# Controller.net
KiCad netlist of a schematic drawn in Altium Designer
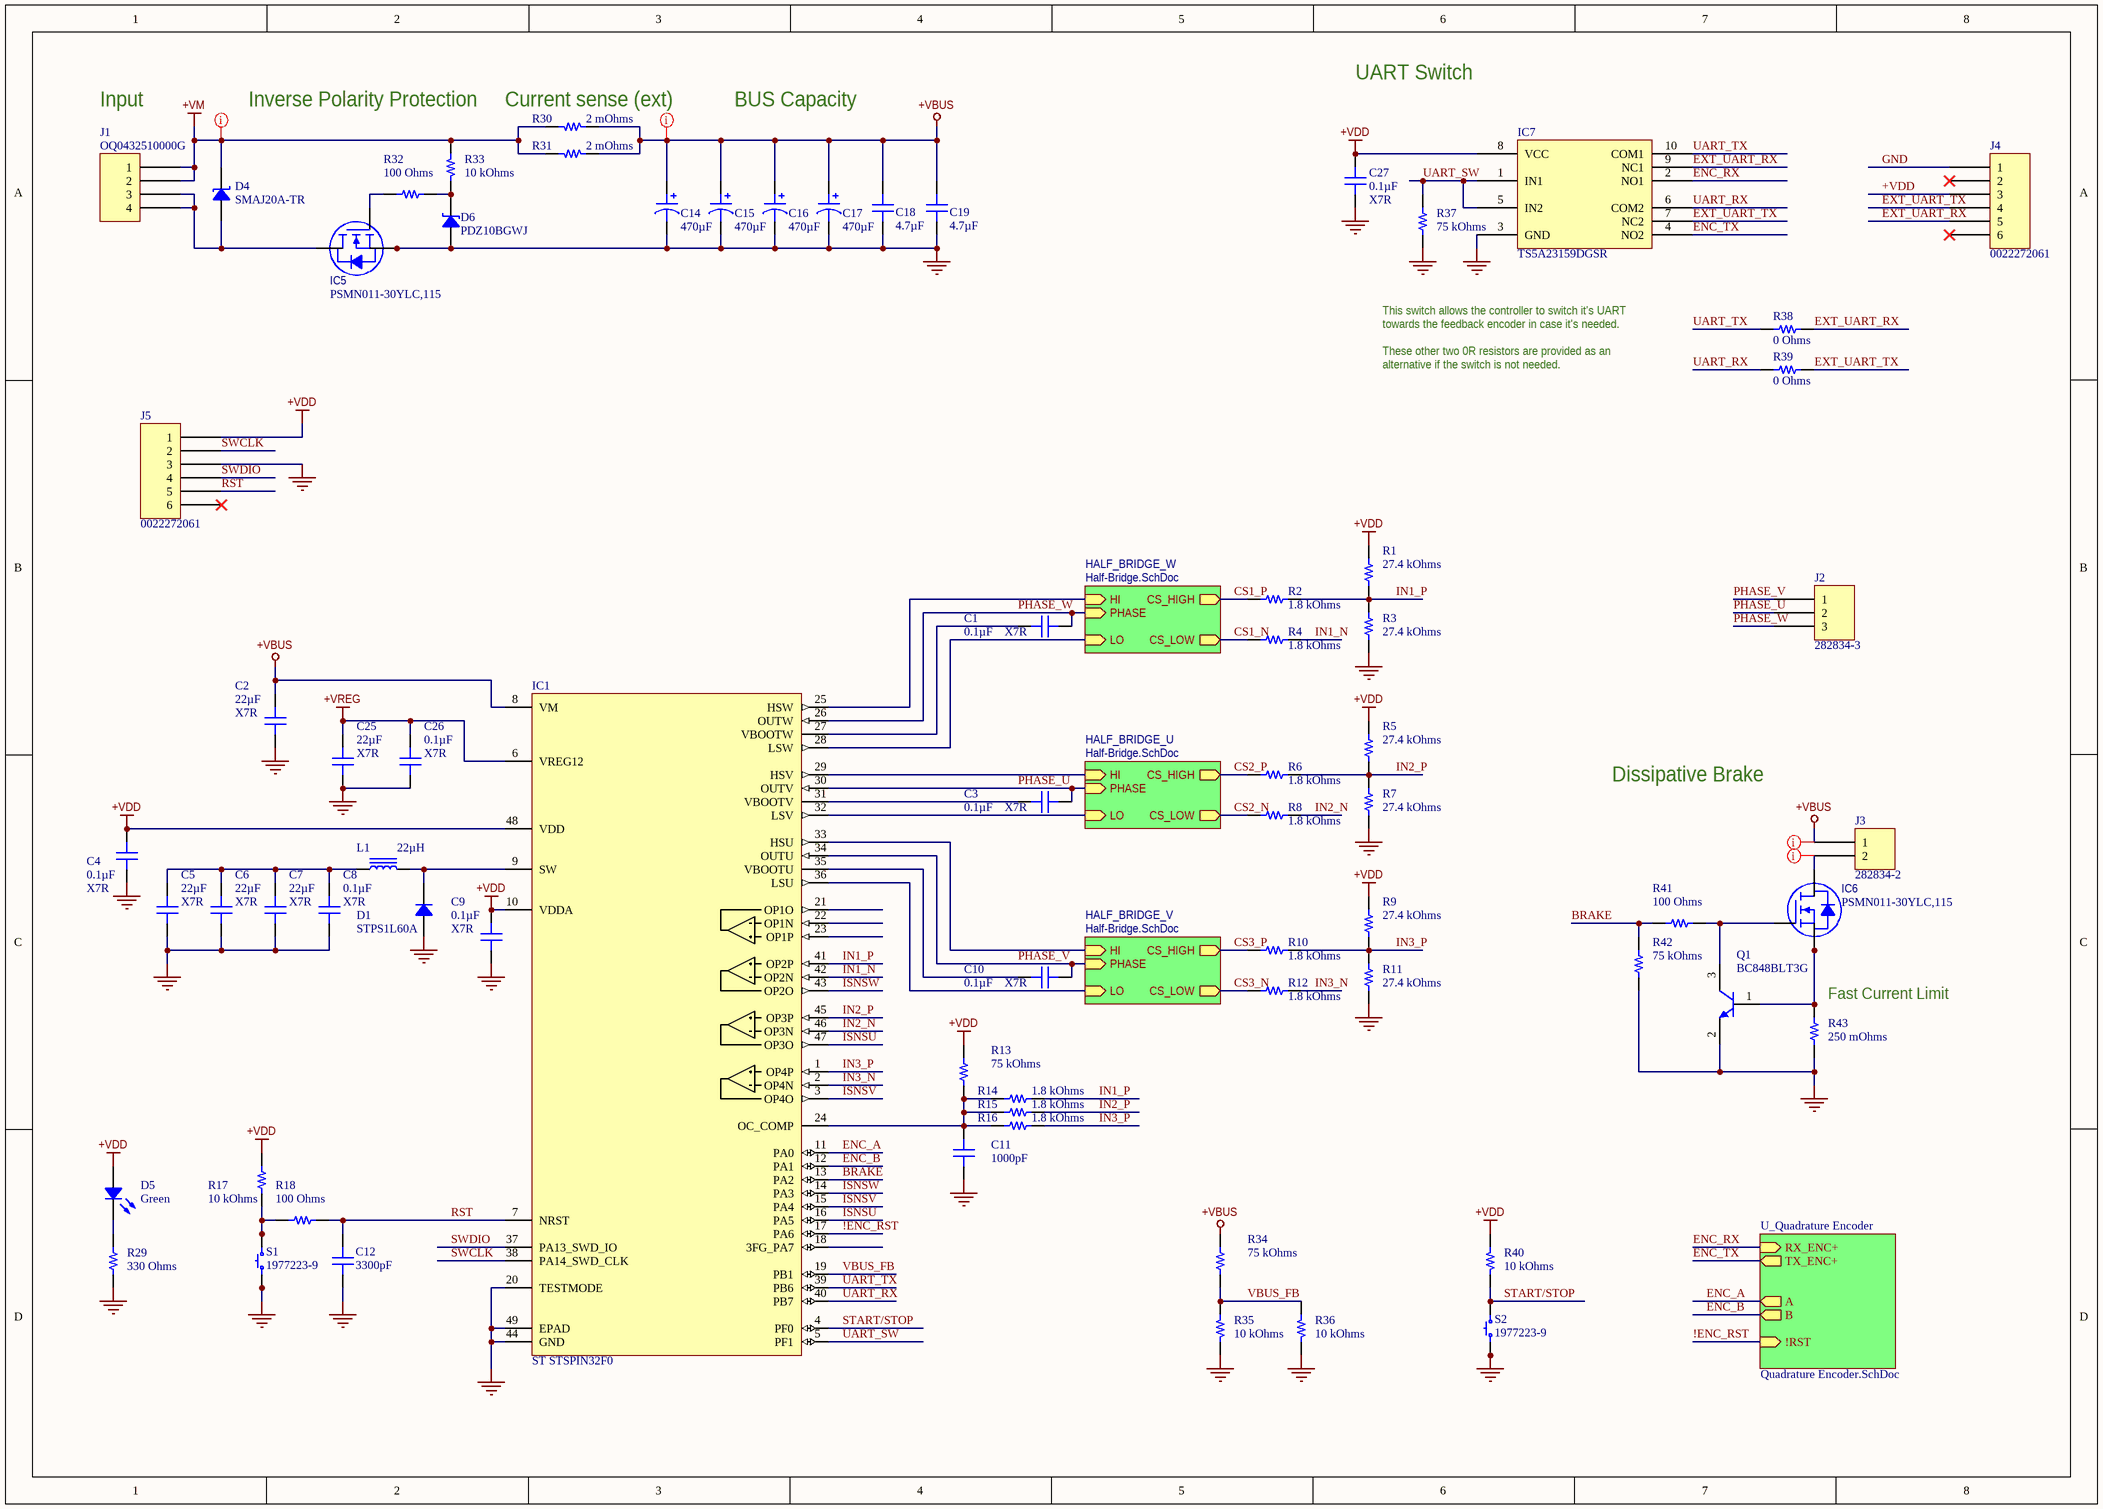
[diagram p0: Controller.SchDoc]

(export (version "E")
  (design (tool "Eeschema 10.0.6"))
  (components
    (comp (ref "C1")
      (value "0.1µF")
      (footprint "CAP 0805_2012")
      (description "CAP CER 0.1UF 50V X7R 0805")
      (fields
        (field (name "PART NUMBER") "CL21B104KBCWPNC")
        (field (name "MANUFACTURER") "Samsung Electro-Mechanics")
        (field (name "TEMPERATURE COEFFICIENT") "X7R")
      )
      (libsource (lib "Celestial Altium Library - altium_library") (part "Capacitor"))
    )
    (comp (ref "C2")
      (value "22µF")
      (footprint "CAP 1206_3216 - 1.8MM")
      (description "CAP CER 22UF 6.3V X7R 1206")
      (fields
        (field (name "PART NUMBER") "GCM31CR70J226KE23L")
        (field (name "MANUFACTURER") "Murata Electronics")
        (field (name "TEMPERATURE COEFFICIENT") "X7R")
      )
      (libsource (lib "Celestial Altium Library - altium_library") (part "Capacitor"))
    )
    (comp (ref "C3")
      (value "0.1µF")
      (footprint "CAP 0805_2012")
      (description "CAP CER 0.1UF 50V X7R 0805")
      (fields
        (field (name "PART NUMBER") "CL21B104KBCWPNC")
        (field (name "MANUFACTURER") "Samsung Electro-Mechanics")
        (field (name "TEMPERATURE COEFFICIENT") "X7R")
      )
      (libsource (lib "Celestial Altium Library - altium_library") (part "Capacitor"))
    )
    (comp (ref "C4")
      (value "0.1µF")
      (footprint "CAP 0805_2012")
      (description "CAP CER 0.1UF 50V X7R 0805")
      (fields
        (field (name "PART NUMBER") "CL21B104KBCWPNC")
        (field (name "MANUFACTURER") "Samsung Electro-Mechanics")
        (field (name "TEMPERATURE COEFFICIENT") "X7R")
      )
      (libsource (lib "Celestial Altium Library - altium_library") (part "Capacitor"))
    )
    (comp (ref "C5")
      (value "22µF")
      (footprint "CAP 1206_3216 - 1.8MM")
      (description "CAP CER 22UF 6.3V X7R 1206")
      (fields
        (field (name "PART NUMBER") "GCM31CR70J226KE23L")
        (field (name "MANUFACTURER") "Murata Electronics")
        (field (name "TEMPERATURE COEFFICIENT") "X7R")
      )
      (libsource (lib "Celestial Altium Library - altium_library") (part "Capacitor"))
    )
    (comp (ref "C6")
      (value "22µF")
      (footprint "CAP 1206_3216 - 1.8MM")
      (description "CAP CER 22UF 6.3V X7R 1206")
      (fields
        (field (name "PART NUMBER") "GCM31CR70J226KE23L")
        (field (name "MANUFACTURER") "Murata Electronics")
        (field (name "TEMPERATURE COEFFICIENT") "X7R")
      )
      (libsource (lib "Celestial Altium Library - altium_library") (part "Capacitor"))
    )
    (comp (ref "C7")
      (value "22µF")
      (footprint "CAP 1206_3216 - 1.8MM")
      (description "CAP CER 22UF 6.3V X7R 1206")
      (fields
        (field (name "PART NUMBER") "GCM31CR70J226KE23L")
        (field (name "MANUFACTURER") "Murata Electronics")
        (field (name "TEMPERATURE COEFFICIENT") "X7R")
      )
      (libsource (lib "Celestial Altium Library - altium_library") (part "Capacitor"))
    )
    (comp (ref "C8")
      (value "0.1µF")
      (footprint "CAP 0805_2012")
      (description "CAP CER 0.1UF 50V X7R 0805")
      (fields
        (field (name "PART NUMBER") "CL21B104KBCWPNC")
        (field (name "MANUFACTURER") "Samsung Electro-Mechanics")
        (field (name "TEMPERATURE COEFFICIENT") "X7R")
      )
      (libsource (lib "Celestial Altium Library - altium_library") (part "Capacitor"))
    )
    (comp (ref "C9")
      (value "0.1µF")
      (footprint "CAP 0805_2012")
      (description "CAP CER 0.1UF 50V X7R 0805")
      (fields
        (field (name "PART NUMBER") "CL21B104KBCWPNC")
        (field (name "MANUFACTURER") "Samsung Electro-Mechanics")
        (field (name "TEMPERATURE COEFFICIENT") "X7R")
      )
      (libsource (lib "Celestial Altium Library - altium_library") (part "Capacitor"))
    )
    (comp (ref "C10")
      (value "0.1µF")
      (footprint "CAP 0805_2012")
      (description "CAP CER 0.1UF 50V X7R 0805")
      (fields
        (field (name "PART NUMBER") "CL21B104KBCWPNC")
        (field (name "MANUFACTURER") "Samsung Electro-Mechanics")
        (field (name "TEMPERATURE COEFFICIENT") "X7R")
      )
      (libsource (lib "Celestial Altium Library - altium_library") (part "Capacitor"))
    )
    (comp (ref "C11")
      (value "1000pF")
      (footprint "CAP 0603_1608")
      (description "CAP CER 0603 1NF 16V X7R 10%")
      (fields (field (name "PART NUMBER") "C0603C102K4RECAUTO") (field (name "MANUFACTURER") "KEMET"))
      (libsource (lib "Celestial Altium Library - altium_library") (part "Capacitor"))
    )
    (comp (ref "C12")
      (value "3300pF")
      (footprint "CAP 0603_1608")
      (description "CAP CER 3300PF 25V NP0 0603")
      (fields (field (name "PART NUMBER") "C0603C332J3GAC7867") (field (name "MANUFACTURER") "KEMET"))
      (libsource (lib "Celestial Altium Library - altium_library") (part "Capacitor"))
    )
    (comp (ref "C14")
      (value "470µF")
      (footprint "CAP ALSMD 8.3MM H10.5MM")
      (description "CAP ALUM 470UF 20% 25V SMD")
      (fields (field (name "PART NUMBER") "25TPV470M8X10.5") (field (name "MANUFACTURER") "Rubycon"))
      (libsource (lib "Celestial Altium Library - altium_library") (part "Polarised Capacitor"))
    )
    (comp (ref "C15")
      (value "470µF")
      (footprint "CAP ALSMD 8.3MM H10.5MM")
      (description "CAP ALUM 470UF 20% 25V SMD")
      (fields (field (name "PART NUMBER") "25TPV470M8X10.5") (field (name "MANUFACTURER") "Rubycon"))
      (libsource (lib "Celestial Altium Library - altium_library") (part "Polarised Capacitor"))
    )
    (comp (ref "C16")
      (value "470µF")
      (footprint "CAP ALSMD 8.3MM H10.5MM")
      (description "CAP ALUM 470UF 20% 25V SMD")
      (fields (field (name "PART NUMBER") "25TPV470M8X10.5") (field (name "MANUFACTURER") "Rubycon"))
      (libsource (lib "Celestial Altium Library - altium_library") (part "Polarised Capacitor"))
    )
    (comp (ref "C17")
      (value "470µF")
      (footprint "CAP ALSMD 8.3MM H10.5MM")
      (description "CAP ALUM 470UF 20% 25V SMD")
      (fields (field (name "PART NUMBER") "25TPV470M8X10.5") (field (name "MANUFACTURER") "Rubycon"))
      (libsource (lib "Celestial Altium Library - altium_library") (part "Polarised Capacitor"))
    )
    (comp (ref "C18")
      (value "4.7µF")
      (footprint "CAP 1206_3216 - 1.8MM")
      (description "CAP CER 4.7UF 25V X7R 1206")
      (fields
        (field (name "PART NUMBER") "GCM31CR71E475KA55L")
        (field (name "MANUFACTURER") "Murata Electronics")
      )
      (libsource (lib "Celestial Altium Library - altium_library") (part "Capacitor"))
    )
    (comp (ref "C19")
      (value "4.7µF")
      (footprint "CAP 1206_3216 - 1.8MM")
      (description "CAP CER 4.7UF 25V X7R 1206")
      (fields
        (field (name "PART NUMBER") "GCM31CR71E475KA55L")
        (field (name "MANUFACTURER") "Murata Electronics")
      )
      (libsource (lib "Celestial Altium Library - altium_library") (part "Capacitor"))
    )
    (comp (ref "C25")
      (value "22µF")
      (footprint "CAP 1206_3216 - 1.8MM")
      (description "CAP CER 22UF 6.3V X7R 1206")
      (fields
        (field (name "PART NUMBER") "GCM31CR70J226KE23L")
        (field (name "MANUFACTURER") "Murata Electronics")
        (field (name "TEMPERATURE COEFFICIENT") "X7R")
      )
      (libsource (lib "Celestial Altium Library - altium_library") (part "Capacitor"))
    )
    (comp (ref "C26")
      (value "0.1µF")
      (footprint "CAP 0805_2012")
      (description "CAP CER 0.1UF 50V X7R 0805")
      (fields
        (field (name "PART NUMBER") "CL21B104KBCWPNC")
        (field (name "MANUFACTURER") "Samsung Electro-Mechanics")
        (field (name "TEMPERATURE COEFFICIENT") "X7R")
      )
      (libsource (lib "Celestial Altium Library - altium_library") (part "Capacitor"))
    )
    (comp (ref "C27")
      (value "0.1µF")
      (footprint "CAP 0805_2012")
      (description "CAP CER 0.1UF 50V X7R 0805")
      (fields
        (field (name "PART NUMBER") "CL21B104KBCWPNC")
        (field (name "MANUFACTURER") "Samsung Electro-Mechanics")
        (field (name "TEMPERATURE COEFFICIENT") "X7R")
      )
      (libsource (lib "Celestial Altium Library - altium_library") (part "Capacitor"))
    )
    (comp (ref "D1")
      (value "STPS1L60A")
      (footprint "DO214AC SMA")
      (description "DIODE SCHOTTKY 60V 1A SMA")
      (fields (field (name "MANUFACTURER") "STMicroelectronics"))
      (libsource (lib "Celestial Altium Library - altium_library") (part "Diode"))
    )
    (comp (ref "D4")
      (value "SMAJ20A-TR")
      (footprint "DO214AC SMA")
      (description "TVS DIODE 20V 42.8V SMA")
      (fields (field (name "MANUFACTURER") "STMicroelectronics"))
      (libsource (lib "Celestial Altium Library - altium_library") (part "DIODE TVS UNI"))
    )
    (comp (ref "D5")
      (value "Green")
      (footprint "LED 0603_1608 GREEN")
      (description "LED GREEN DIFFUSED 0603 SMD")
      (fields (field (name "PART NUMBER") "SML-D12P8WT86") (field (name "MANUFACTURER") "Rohm Semiconductor"))
      (libsource (lib "Celestial Altium Library - altium_library") (part "LED"))
    )
    (comp (ref "D6")
      (value "PDZ10BGWJ")
      (footprint "SOD-123")
      (description "DIODE ZENER 10V 365MW SOD123")
      (fields (field (name "MANUFACTURER") "Nexperia USA Inc.") (field (name "TOLERANCE") "±2.2%"))
      (libsource (lib "Celestial Altium Library - altium_library") (part "Diode Zener"))
    )
    (comp (ref "IC1")
      (value "ST STSPIN32F0")
      (footprint "PCB - LEADLESS - QFN - ST VFQFPN48 EP 5x5MM:ST VFQFPN48EP 7x7MM")
      (libsource (lib "SCH - MICROCONTROLLER - ST STSPIN32F0") (part "ST STSPIN32F0"))
    )
    (comp (ref "IC5")
      (value "PSMN011-30YLC,115")
      (footprint "NXP LFPAK56 SOT669")
      (description "MOSFET N-CH 30V 37A LFPAK")
      (fields (field (name "MANUFACTURER") "Nexperia USA Inc."))
      (libsource (lib "") (part "NEXPERIA PSMN LFPAK MOSFET N-CH_1"))
    )
    (comp (ref "IC6")
      (value "PSMN011-30YLC,115")
      (footprint "NXP LFPAK56 SOT669")
      (description "MOSFET N-CH 30V 37A LFPAK")
      (fields (field (name "MANUFACTURER") "Nexperia USA Inc."))
      (libsource (lib "Celestial Altium Library - altium_library") (part "NEXPERIA PSMN LFPAK MOSFET N-CH"))
    )
    (comp (ref "IC7")
      (value "TS5A23159DGSR")
      (footprint "TI MSOP-10 DGS")
      (description "IC SWITCH SPDT DUAL 10VSSOP")
      (fields (field (name "MANUFACTURER") "Texas Instruments"))
      (libsource (lib "Celestial Altium Library - altium_library") (part "TI TS5A23159"))
    )
    (comp (ref "J1")
      (value "OQ0432510000G")
      (footprint "FCI 06-381-4PIN")
      (description "TERM BLOCK HDR 4POS 90DEG 3.81MM")
      (fields (field (name "MANUFACTURER") "Amphenol Anytek"))
      (libsource (lib "Celestial Altium Library - altium_library") (part "4 Pin"))
    )
    (comp (ref "J2")
      (value "282834-3")
      (footprint "TE 282834-3")
      (description "TERM BLK 3P SIDE ENT 2.54MM PCB")
      (fields (field (name "MANUFACTURER") "TE Connectivity AMP Connectors") (field (name "VOLTAGE") "150V"))
      (libsource (lib "Celestial Altium Library - altium_library") (part "3 Pin"))
    )
    (comp (ref "J3")
      (value "282834-2")
      (footprint "TE 282834-2")
      (description "TERM BLK 2P SIDE ENT 2.54MM PCB")
      (fields (field (name "MANUFACTURER") "TE Connectivity AMP Connectors") (field (name "VOLTAGE") "150V"))
      (libsource (lib "Celestial Altium Library - altium_library") (part "2 Pin"))
    )
    (comp (ref "J4")
      (value "0022272061")
      (footprint "MOLEX KK 0022272061")
      (description "CONN HEADER VERT 6POS 2.54MM")
      (fields (field (name "MANUFACTURER") "Molex"))
      (libsource (lib "Celestial Altium Library - altium_library") (part "6 Pin"))
    )
    (comp (ref "J5")
      (value "0022272061")
      (footprint "MOLEX KK 0022272061")
      (description "CONN HEADER VERT 6POS 2.54MM")
      (fields (field (name "MANUFACTURER") "Molex"))
      (libsource (lib "") (part "6 Pin_1"))
    )
    (comp (ref "L1")
      (value "22µH")
      (footprint "BOURNS SRN3015")
      (description "FIXED IND 22UH 600MA 622MOHM SMD")
      (fields (field (name "PART NUMBER") "SRN3015-220M") (field (name "MANUFACTURER") "Bourns Inc."))
      (libsource (lib "Celestial Altium Library - altium_library") (part "Inductor"))
    )
    (comp (ref "Q1")
      (value "BC848BLT3G")
      (footprint "ON SEMI SOT-23-3")
      (description "TRANS NPN 30V 0.1A SOT-23")
      (fields (field (name "MANUFACTURER") "ON Semiconductor"))
      (libsource (lib "Celestial Altium Library - altium_library") (part "ON SEMI NPN SOT-23-3"))
    )
    (comp (ref "R1")
      (value "27.4 kOhms")
      (footprint "RES 0603_1608")
      (description "RES SMD 27.4K OHM 1% 1/10W 0603")
      (fields
        (field (name "PART NUMBER") "ERJ-3EKF2742V")
        (field (name "MANUFACTURER") "Panasonic Electronic Components")
      )
      (libsource (lib "Celestial Altium Library - altium_library") (part "Resistor"))
    )
    (comp (ref "R2")
      (value "1.8 kOhms")
      (footprint "RES 0603_1608")
      (description "RES SMD 1.8K OHM 1% 1/4W 0603")
      (fields
        (field (name "PART NUMBER") "ERJ-PA3F1801V")
        (field (name "MANUFACTURER") "Panasonic Electronic Components")
      )
      (libsource (lib "Celestial Altium Library - altium_library") (part "Resistor"))
    )
    (comp (ref "R3")
      (value "27.4 kOhms")
      (footprint "RES 0603_1608")
      (description "RES SMD 27.4K OHM 1% 1/10W 0603")
      (fields
        (field (name "PART NUMBER") "ERJ-3EKF2742V")
        (field (name "MANUFACTURER") "Panasonic Electronic Components")
      )
      (libsource (lib "Celestial Altium Library - altium_library") (part "Resistor"))
    )
    (comp (ref "R4")
      (value "1.8 kOhms")
      (footprint "RES 0603_1608")
      (description "RES SMD 1.8K OHM 1% 1/4W 0603")
      (fields
        (field (name "PART NUMBER") "ERJ-PA3F1801V")
        (field (name "MANUFACTURER") "Panasonic Electronic Components")
      )
      (libsource (lib "Celestial Altium Library - altium_library") (part "Resistor"))
    )
    (comp (ref "R5")
      (value "27.4 kOhms")
      (footprint "RES 0603_1608")
      (description "RES SMD 27.4K OHM 1% 1/10W 0603")
      (fields
        (field (name "PART NUMBER") "ERJ-3EKF2742V")
        (field (name "MANUFACTURER") "Panasonic Electronic Components")
      )
      (libsource (lib "Celestial Altium Library - altium_library") (part "Resistor"))
    )
    (comp (ref "R6")
      (value "1.8 kOhms")
      (footprint "RES 0603_1608")
      (description "RES SMD 1.8K OHM 1% 1/4W 0603")
      (fields
        (field (name "PART NUMBER") "ERJ-PA3F1801V")
        (field (name "MANUFACTURER") "Panasonic Electronic Components")
      )
      (libsource (lib "Celestial Altium Library - altium_library") (part "Resistor"))
    )
    (comp (ref "R7")
      (value "27.4 kOhms")
      (footprint "RES 0603_1608")
      (description "RES SMD 27.4K OHM 1% 1/10W 0603")
      (fields
        (field (name "PART NUMBER") "ERJ-3EKF2742V")
        (field (name "MANUFACTURER") "Panasonic Electronic Components")
      )
      (libsource (lib "Celestial Altium Library - altium_library") (part "Resistor"))
    )
    (comp (ref "R8")
      (value "1.8 kOhms")
      (footprint "RES 0603_1608")
      (description "RES SMD 1.8K OHM 1% 1/4W 0603")
      (fields
        (field (name "PART NUMBER") "ERJ-PA3F1801V")
        (field (name "MANUFACTURER") "Panasonic Electronic Components")
      )
      (libsource (lib "Celestial Altium Library - altium_library") (part "Resistor"))
    )
    (comp (ref "R9")
      (value "27.4 kOhms")
      (footprint "RES 0603_1608")
      (description "RES SMD 27.4K OHM 1% 1/10W 0603")
      (fields
        (field (name "PART NUMBER") "ERJ-3EKF2742V")
        (field (name "MANUFACTURER") "Panasonic Electronic Components")
      )
      (libsource (lib "Celestial Altium Library - altium_library") (part "Resistor"))
    )
    (comp (ref "R10")
      (value "1.8 kOhms")
      (footprint "RES 0603_1608")
      (description "RES SMD 1.8K OHM 1% 1/4W 0603")
      (fields
        (field (name "PART NUMBER") "ERJ-PA3F1801V")
        (field (name "MANUFACTURER") "Panasonic Electronic Components")
      )
      (libsource (lib "Celestial Altium Library - altium_library") (part "Resistor"))
    )
    (comp (ref "R11")
      (value "27.4 kOhms")
      (footprint "RES 0603_1608")
      (description "RES SMD 27.4K OHM 1% 1/10W 0603")
      (fields
        (field (name "PART NUMBER") "ERJ-3EKF2742V")
        (field (name "MANUFACTURER") "Panasonic Electronic Components")
      )
      (libsource (lib "Celestial Altium Library - altium_library") (part "Resistor"))
    )
    (comp (ref "R12")
      (value "1.8 kOhms")
      (footprint "RES 0603_1608")
      (description "RES SMD 1.8K OHM 1% 1/4W 0603")
      (fields
        (field (name "PART NUMBER") "ERJ-PA3F1801V")
        (field (name "MANUFACTURER") "Panasonic Electronic Components")
      )
      (libsource (lib "Celestial Altium Library - altium_library") (part "Resistor"))
    )
    (comp (ref "R13")
      (value "75 kOhms")
      (footprint "RES 0603_1608")
      (description "RES SMD 75K OHM 1% 1/10W 0603")
      (fields
        (field (name "PART NUMBER") "ERJ-3EKF7502V")
        (field (name "MANUFACTURER") "Panasonic Electronic Components")
      )
      (libsource (lib "Celestial Altium Library - altium_library") (part "Resistor"))
    )
    (comp (ref "R14")
      (value "1.8 kOhms")
      (footprint "RES 0603_1608")
      (description "RES SMD 1.8K OHM 1% 1/4W 0603")
      (fields
        (field (name "PART NUMBER") "ERJ-PA3F1801V")
        (field (name "MANUFACTURER") "Panasonic Electronic Components")
      )
      (libsource (lib "Celestial Altium Library - altium_library") (part "Resistor"))
    )
    (comp (ref "R15")
      (value "1.8 kOhms")
      (footprint "RES 0603_1608")
      (description "RES SMD 1.8K OHM 1% 1/4W 0603")
      (fields
        (field (name "PART NUMBER") "ERJ-PA3F1801V")
        (field (name "MANUFACTURER") "Panasonic Electronic Components")
      )
      (libsource (lib "Celestial Altium Library - altium_library") (part "Resistor"))
    )
    (comp (ref "R16")
      (value "1.8 kOhms")
      (footprint "RES 0603_1608")
      (description "RES SMD 1.8K OHM 1% 1/4W 0603")
      (fields
        (field (name "PART NUMBER") "ERJ-PA3F1801V")
        (field (name "MANUFACTURER") "Panasonic Electronic Components")
      )
      (libsource (lib "Celestial Altium Library - altium_library") (part "Resistor"))
    )
    (comp (ref "R17")
      (value "10 kOhms")
      (footprint "RES 0603_1608")
      (description "RES SMD 10K OHM 1% 1/4W 0603")
      (fields (field (name "PART NUMBER") "ESR03EZPF1002") (field (name "MANUFACTURER") "Rohm Semiconductor"))
      (libsource (lib "Celestial Altium Library - altium_library") (part "Resistor"))
    )
    (comp (ref "R18")
      (value "100 Ohms")
      (footprint "RES 0603_1608")
      (description "RES 100 OHM 1% 1/8W 0603")
      (fields
        (field (name "PART NUMBER") "RNCP0603FTD100R")
        (field (name "MANUFACTURER") "Stackpole Electronics Inc")
      )
      (libsource (lib "Celestial Altium Library - altium_library") (part "Resistor"))
    )
    (comp (ref "R29")
      (value "330 Ohms")
      (footprint "RES 0603_1608")
      (description "RES SMD 330 OHM 1% 1/5W 0603")
      (fields
        (field (name "PART NUMBER") "CRGH0603F330R")
        (field (name "MANUFACTURER") "TE Connectivity Passive Product")
      )
      (libsource (lib "Celestial Altium Library - altium_library") (part "Resistor"))
    )
    (comp (ref "R30")
      (value "2 mOhms")
      (footprint "RES 1210_3225")
      (description "RES 0.002 OHM 1% 1W 1210")
      (fields
        (field (name "PART NUMBER") "PMR25HZPFV2L00")
        (field (name "MANUFACTURER") "Rohm Semiconductor")
      )
      (libsource (lib "Celestial Altium Library - altium_library") (part "Resistor"))
    )
    (comp (ref "R31")
      (value "2 mOhms")
      (footprint "RES 1210_3225")
      (description "RES 0.002 OHM 1% 1W 1210")
      (fields
        (field (name "PART NUMBER") "PMR25HZPFV2L00")
        (field (name "MANUFACTURER") "Rohm Semiconductor")
      )
      (libsource (lib "Celestial Altium Library - altium_library") (part "Resistor"))
    )
    (comp (ref "R32")
      (value "100 Ohms")
      (footprint "RES 0603_1608")
      (description "RES 100 OHM 1% 1/8W 0603")
      (fields
        (field (name "PART NUMBER") "RNCP0603FTD100R")
        (field (name "MANUFACTURER") "Stackpole Electronics Inc")
      )
      (libsource (lib "Celestial Altium Library - altium_library") (part "Resistor"))
    )
    (comp (ref "R33")
      (value "10 kOhms")
      (footprint "RES 0603_1608")
      (description "RES SMD 10K OHM 1% 1/4W 0603")
      (fields (field (name "PART NUMBER") "ESR03EZPF1002") (field (name "MANUFACTURER") "Rohm Semiconductor"))
      (libsource (lib "Celestial Altium Library - altium_library") (part "Resistor"))
    )
    (comp (ref "R34")
      (value "75 kOhms")
      (footprint "RES 0603_1608")
      (description "RES SMD 75K OHM 1% 1/10W 0603")
      (fields
        (field (name "PART NUMBER") "ERJ-3EKF7502V")
        (field (name "MANUFACTURER") "Panasonic Electronic Components")
      )
      (libsource (lib "Celestial Altium Library - altium_library") (part "Resistor"))
    )
    (comp (ref "R35")
      (value "10 kOhms")
      (footprint "RES 0603_1608")
      (description "RES SMD 10K OHM 1% 1/4W 0603")
      (fields (field (name "PART NUMBER") "ESR03EZPF1002") (field (name "MANUFACTURER") "Rohm Semiconductor"))
      (libsource (lib "Celestial Altium Library - altium_library") (part "Resistor"))
    )
    (comp (ref "R36")
      (value "10 kOhms")
      (footprint "RES 0603_1608")
      (description "RES SMD 10K OHM 1% 1/4W 0603")
      (fields (field (name "PART NUMBER") "ESR03EZPF1002") (field (name "MANUFACTURER") "Rohm Semiconductor"))
      (libsource (lib "Celestial Altium Library - altium_library") (part "Resistor"))
    )
    (comp (ref "R37")
      (value "75 kOhms")
      (footprint "RES 0603_1608")
      (description "RES SMD 75K OHM 1% 1/10W 0603")
      (fields
        (field (name "PART NUMBER") "ERJ-3EKF7502V")
        (field (name "MANUFACTURER") "Panasonic Electronic Components")
      )
      (libsource (lib "Celestial Altium Library - altium_library") (part "Resistor"))
    )
    (comp (ref "R38")
      (value "0 Ohms")
      (footprint "RES 0603_1608")
      (description "RES SMD 0 OHM JUMPER 1/4W 0603")
      (fields (field (name "PART NUMBER") "CRCW06030000Z0EAHP") (field (name "MANUFACTURER") "Vishay Dale"))
      (libsource (lib "Celestial Altium Library - altium_library") (part "Resistor"))
    )
    (comp (ref "R39")
      (value "0 Ohms")
      (footprint "RES 0603_1608")
      (description "RES SMD 0 OHM JUMPER 1/4W 0603")
      (fields (field (name "PART NUMBER") "CRCW06030000Z0EAHP") (field (name "MANUFACTURER") "Vishay Dale"))
      (libsource (lib "Celestial Altium Library - altium_library") (part "Resistor"))
    )
    (comp (ref "R40")
      (value "10 kOhms")
      (footprint "RES 0603_1608")
      (description "RES SMD 10K OHM 1% 1/4W 0603")
      (fields (field (name "PART NUMBER") "ESR03EZPF1002") (field (name "MANUFACTURER") "Rohm Semiconductor"))
      (libsource (lib "Celestial Altium Library - altium_library") (part "Resistor"))
    )
    (comp (ref "R41")
      (value "100 Ohms")
      (footprint "RES 0603_1608")
      (description "RES 100 OHM 1% 1/8W 0603")
      (fields
        (field (name "PART NUMBER") "RNCP0603FTD100R")
        (field (name "MANUFACTURER") "Stackpole Electronics Inc")
      )
      (libsource (lib "Celestial Altium Library - altium_library") (part "Resistor"))
    )
    (comp (ref "R42")
      (value "75 kOhms")
      (footprint "RES 0603_1608")
      (description "RES SMD 75K OHM 1% 1/10W 0603")
      (fields
        (field (name "PART NUMBER") "ERJ-3EKF7502V")
        (field (name "MANUFACTURER") "Panasonic Electronic Components")
      )
      (libsource (lib "Celestial Altium Library - altium_library") (part "Resistor"))
    )
    (comp (ref "R43")
      (value "250 mOhms")
      (footprint "RES 2512_6432")
      (description "RES 0.25 OHM 1% 2W 2512")
      (fields (field (name "PART NUMBER") "CRM2512-FX-R250ELF") (field (name "MANUFACTURER") "Bourns Inc."))
      (libsource (lib "Celestial Altium Library - altium_library") (part "Resistor"))
    )
    (comp (ref "S1")
      (value "1977223-9")
      (footprint "TE FSM4JSMA")
      (description "SWITCH TACTILE SPST-NO 0.05A 24V")
      (fields (field (name "MANUFACTURER") "TE Connectivity ALCOSWITCH Switches"))
      (libsource (lib "Celestial Altium Library - altium_library") (part "SPST-NO 4 PIN"))
    )
    (comp (ref "S2")
      (value "1977223-9")
      (footprint "TE FSM4JSMA")
      (description "SWITCH TACTILE SPST-NO 0.05A 24V")
      (fields (field (name "MANUFACTURER") "TE Connectivity ALCOSWITCH Switches"))
      (libsource (lib "Celestial Altium Library - altium_library") (part "SPST-NO 4 PIN"))
    )
  )
  (nets
    (net (code "1") (name "+VBUS") (class "Default")
      (node (ref "C14") (pin "1") (pinfunction "1_1") (pintype "passive"))
      (node (ref "C15") (pin "1") (pinfunction "1_1") (pintype "passive"))
      (node (ref "C16") (pin "1") (pinfunction "1_1") (pintype "passive"))
      (node (ref "C17") (pin "1") (pinfunction "1_1") (pintype "passive"))
      (node (ref "C18") (pin "2") (pinfunction "2_2") (pintype "passive"))
      (node (ref "C19") (pin "2") (pinfunction "2_2") (pintype "passive"))
      (node (ref "C2") (pin "2") (pinfunction "2_2") (pintype "passive"))
      (node (ref "IC1") (pin "8") (pinfunction "VM_8") (pintype "power_in"))
      (node (ref "J3") (pin "1") (pinfunction "1_1") (pintype "passive"))
      (node (ref "R30") (pin "1") (pinfunction "1_1") (pintype "passive"))
      (node (ref "R31") (pin "1") (pinfunction "1_1") (pintype "passive"))
      (node (ref "R34") (pin "2") (pinfunction "2_2") (pintype "passive"))
    )
    (net (code "2") (name "+VDD") (class "Default")
      (node (ref "C27") (pin "1") (pinfunction "1_1") (pintype "passive"))
      (node (ref "C4") (pin "1") (pinfunction "1_1") (pintype "passive"))
      (node (ref "C9") (pin "1") (pinfunction "1_1") (pintype "passive"))
      (node (ref "D5") (pin "1") (pinfunction "1_1") (pintype "passive"))
      (node (ref "IC1") (pin "10") (pinfunction "VDDA_10") (pintype "power_in"))
      (node (ref "IC1") (pin "48") (pinfunction "VDD_48") (pintype "power_in"))
      (node (ref "IC7") (pin "8") (pinfunction "VCC_8") (pintype "passive"))
      (node (ref "J4") (pin "3") (pinfunction "3_3") (pintype "passive"))
      (node (ref "J5") (pin "1") (pinfunction "1_1") (pintype "passive"))
      (node (ref "R1") (pin "2") (pinfunction "2_2") (pintype "passive"))
      (node (ref "R13") (pin "2") (pinfunction "2_2") (pintype "passive"))
      (node (ref "R17") (pin "2") (pinfunction "2_2") (pintype "passive"))
      (node (ref "R40") (pin "2") (pinfunction "2_2") (pintype "passive"))
      (node (ref "R5") (pin "2") (pinfunction "2_2") (pintype "passive"))
      (node (ref "R9") (pin "2") (pinfunction "2_2") (pintype "passive"))
    )
    (net (code "3") (name "+VM") (class "Default")
      (node (ref "D4") (pin "2") (pinfunction "2_2") (pintype "passive"))
      (node (ref "J1") (pin "1") (pinfunction "1_1") (pintype "passive"))
      (node (ref "J1") (pin "2") (pinfunction "2_2") (pintype "passive"))
      (node (ref "R30") (pin "2") (pinfunction "2_2") (pintype "passive"))
      (node (ref "R31") (pin "2") (pinfunction "2_2") (pintype "passive"))
      (node (ref "R33") (pin "2") (pinfunction "2_2") (pintype "passive"))
    )
    (net (code "4") (name "+VREG") (class "Default")
      (node (ref "C25") (pin "2") (pinfunction "2_2") (pintype "passive"))
      (node (ref "C26") (pin "1") (pinfunction "1_1") (pintype "passive"))
      (node (ref "IC1") (pin "6") (pinfunction "VREG12_6") (pintype "power_in"))
    )
    (net (code "5") (name "/!ENC_RST") (class "Default")
      (node (ref "IC1") (pin "17") (pinfunction "PA6_17") (pintype "bidirectional"))
    )
    (net (code "6") (name "/BRAKE") (class "Default")
      (node (ref "IC1") (pin "13") (pinfunction "PA2_13") (pintype "bidirectional"))
      (node (ref "R41") (pin "1") (pinfunction "1_1") (pintype "passive"))
      (node (ref "R42") (pin "2") (pinfunction "2_2") (pintype "passive"))
    )
    (net (code "7") (name "/CS1_N") (class "Default")
      (node (ref "R4") (pin "1") (pinfunction "1_1") (pintype "passive"))
    )
    (net (code "8") (name "/CS1_P") (class "Default")
      (node (ref "R2") (pin "1") (pinfunction "1_1") (pintype "passive"))
    )
    (net (code "9") (name "/CS2_N") (class "Default")
      (node (ref "R8") (pin "1") (pinfunction "1_1") (pintype "passive"))
    )
    (net (code "10") (name "/CS2_P") (class "Default")
      (node (ref "R6") (pin "1") (pinfunction "1_1") (pintype "passive"))
    )
    (net (code "11") (name "/CS3_N") (class "Default")
      (node (ref "R12") (pin "1") (pinfunction "1_1") (pintype "passive"))
    )
    (net (code "12") (name "/CS3_P") (class "Default")
      (node (ref "R10") (pin "1") (pinfunction "1_1") (pintype "passive"))
    )
    (net (code "13") (name "/ENC_A") (class "Default")
      (node (ref "IC1") (pin "11") (pinfunction "PA0_11") (pintype "bidirectional"))
    )
    (net (code "14") (name "/ENC_B") (class "Default")
      (node (ref "IC1") (pin "12") (pinfunction "PA1_12") (pintype "bidirectional"))
    )
    (net (code "15") (name "/ENC_RX") (class "Default")
      (node (ref "IC7") (pin "2") (pinfunction "NO1_2") (pintype "passive"))
    )
    (net (code "16") (name "/ENC_TX") (class "Default")
      (node (ref "IC7") (pin "4") (pinfunction "NO2_4") (pintype "passive"))
    )
    (net (code "17") (name "/EXT_UART_RX") (class "Default")
      (node (ref "IC7") (pin "9") (pinfunction "NC1_9") (pintype "passive"))
      (node (ref "J4") (pin "5") (pinfunction "5_5") (pintype "passive"))
      (node (ref "R38") (pin "2") (pinfunction "2_2") (pintype "passive"))
    )
    (net (code "18") (name "/EXT_UART_TX") (class "Default")
      (node (ref "IC7") (pin "7") (pinfunction "NC2_7") (pintype "passive"))
      (node (ref "J4") (pin "4") (pinfunction "4_4") (pintype "passive"))
      (node (ref "R39") (pin "2") (pinfunction "2_2") (pintype "passive"))
    )
    (net (code "19") (name "/HI") (class "Default")
      (node (ref "IC1") (pin "33") (pinfunction "HSU_33") (pintype "output"))
    )
    (net (code "20") (name "/HI_1") (class "Default")
      (node (ref "IC1") (pin "25") (pinfunction "HSW_25") (pintype "output"))
    )
    (net (code "21") (name "/HI_2") (class "Default")
      (node (ref "IC1") (pin "29") (pinfunction "HSV_29") (pintype "output"))
    )
    (net (code "22") (name "/IN1_N") (class "Default")
      (node (ref "IC1") (pin "42") (pinfunction "OP2N_42") (pintype "input"))
      (node (ref "R4") (pin "2") (pinfunction "2_2") (pintype "passive"))
    )
    (net (code "23") (name "/IN1_P") (class "Default")
      (node (ref "IC1") (pin "41") (pinfunction "OP2P_41") (pintype "input"))
      (node (ref "R1") (pin "1") (pinfunction "1_1") (pintype "passive"))
      (node (ref "R14") (pin "2") (pinfunction "2_2") (pintype "passive"))
      (node (ref "R2") (pin "2") (pinfunction "2_2") (pintype "passive"))
      (node (ref "R3") (pin "2") (pinfunction "2_2") (pintype "passive"))
    )
    (net (code "24") (name "/IN2_N") (class "Default")
      (node (ref "IC1") (pin "46") (pinfunction "OP3N_46") (pintype "input"))
      (node (ref "R8") (pin "2") (pinfunction "2_2") (pintype "passive"))
    )
    (net (code "25") (name "/IN2_P") (class "Default")
      (node (ref "IC1") (pin "45") (pinfunction "OP3P_45") (pintype "input"))
      (node (ref "R15") (pin "2") (pinfunction "2_2") (pintype "passive"))
      (node (ref "R5") (pin "1") (pinfunction "1_1") (pintype "passive"))
      (node (ref "R6") (pin "2") (pinfunction "2_2") (pintype "passive"))
      (node (ref "R7") (pin "2") (pinfunction "2_2") (pintype "passive"))
    )
    (net (code "26") (name "/IN3_N") (class "Default")
      (node (ref "IC1") (pin "2") (pinfunction "OP4N_2") (pintype "input"))
      (node (ref "R12") (pin "2") (pinfunction "2_2") (pintype "passive"))
    )
    (net (code "27") (name "/IN3_P") (class "Default")
      (node (ref "IC1") (pin "1") (pinfunction "OP4P_1") (pintype "input"))
      (node (ref "R10") (pin "2") (pinfunction "2_2") (pintype "passive"))
      (node (ref "R11") (pin "2") (pinfunction "2_2") (pintype "passive"))
      (node (ref "R16") (pin "2") (pinfunction "2_2") (pintype "passive"))
      (node (ref "R9") (pin "1") (pinfunction "1_1") (pintype "passive"))
    )
    (net (code "28") (name "/ISNSU") (class "Default")
      (node (ref "IC1") (pin "16") (pinfunction "PA5_16") (pintype "bidirectional"))
      (node (ref "IC1") (pin "47") (pinfunction "OP3O_47") (pintype "output"))
    )
    (net (code "29") (name "/ISNSV") (class "Default")
      (node (ref "IC1") (pin "15") (pinfunction "PA4_15") (pintype "bidirectional"))
      (node (ref "IC1") (pin "3") (pinfunction "OP4O_3") (pintype "output"))
    )
    (net (code "30") (name "/ISNSW") (class "Default")
      (node (ref "IC1") (pin "14") (pinfunction "PA3_14") (pintype "bidirectional"))
      (node (ref "IC1") (pin "43") (pinfunction "OP2O_43") (pintype "output"))
    )
    (net (code "31") (name "/LO") (class "Default")
      (node (ref "IC1") (pin "36") (pinfunction "LSU_36") (pintype "output"))
    )
    (net (code "32") (name "/LO_1") (class "Default")
      (node (ref "IC1") (pin "28") (pinfunction "LSW_28") (pintype "output"))
    )
    (net (code "33") (name "/LO_2") (class "Default")
      (node (ref "IC1") (pin "32") (pinfunction "LSV_32") (pintype "output"))
    )
    (net (code "34") (name "/PHASE_U") (class "Default")
      (node (ref "C3") (pin "1") (pinfunction "1_1") (pintype "passive"))
      (node (ref "IC1") (pin "30") (pinfunction "OUTV_30") (pintype "input"))
      (node (ref "J2") (pin "2") (pinfunction "2_2") (pintype "passive"))
    )
    (net (code "35") (name "/PHASE_V") (class "Default")
      (node (ref "C10") (pin "1") (pinfunction "1_1") (pintype "passive"))
      (node (ref "IC1") (pin "34") (pinfunction "OUTU_34") (pintype "input"))
      (node (ref "J2") (pin "1") (pinfunction "1_1") (pintype "passive"))
    )
    (net (code "36") (name "/PHASE_W") (class "Default")
      (node (ref "C1") (pin "1") (pinfunction "1_1") (pintype "passive"))
      (node (ref "IC1") (pin "26") (pinfunction "OUTW_26") (pintype "input"))
      (node (ref "J2") (pin "3") (pinfunction "3_3") (pintype "passive"))
    )
    (net (code "37") (name "/RST") (class "Default")
      (node (ref "C12") (pin "2") (pinfunction "2_2") (pintype "passive"))
      (node (ref "IC1") (pin "7") (pinfunction "NRST_7") (pintype "passive"))
      (node (ref "J5") (pin "5") (pinfunction "5_5") (pintype "passive"))
      (node (ref "R18") (pin "2") (pinfunction "2_2") (pintype "passive"))
    )
    (net (code "38") (name "/START{slash}STOP") (class "Default")
      (node (ref "IC1") (pin "4") (pinfunction "PF0_4") (pintype "bidirectional"))
      (node (ref "R40") (pin "1") (pinfunction "1_1") (pintype "passive"))
      (node (ref "S2") (pin "3") (pinfunction "3_3") (pintype "passive"))
      (node (ref "S2") (pin "4") (pinfunction "4_4") (pintype "passive"))
    )
    (net (code "39") (name "/SWCLK") (class "Default")
      (node (ref "IC1") (pin "38") (pinfunction "PA14_SWD_CLK_38") (pintype "passive"))
      (node (ref "J5") (pin "2") (pinfunction "2_2") (pintype "passive"))
    )
    (net (code "40") (name "/SWDIO") (class "Default")
      (node (ref "IC1") (pin "37") (pinfunction "PA13_SWD_IO_37") (pintype "passive"))
      (node (ref "J5") (pin "4") (pinfunction "4_4") (pintype "passive"))
    )
    (net (code "41") (name "/UART_RX") (class "Default")
      (node (ref "IC1") (pin "40") (pinfunction "PB7_40") (pintype "bidirectional"))
      (node (ref "IC7") (pin "6") (pinfunction "COM2_6") (pintype "passive"))
      (node (ref "R39") (pin "1") (pinfunction "1_1") (pintype "passive"))
    )
    (net (code "42") (name "/UART_SW") (class "Default")
      (node (ref "IC1") (pin "5") (pinfunction "PF1_5") (pintype "bidirectional"))
      (node (ref "IC7") (pin "1") (pinfunction "IN1_1") (pintype "passive"))
      (node (ref "IC7") (pin "5") (pinfunction "IN2_5") (pintype "passive"))
      (node (ref "R37") (pin "2") (pinfunction "2_2") (pintype "passive"))
    )
    (net (code "43") (name "/UART_TX") (class "Default")
      (node (ref "IC1") (pin "39") (pinfunction "PB6_39") (pintype "bidirectional"))
      (node (ref "IC7") (pin "10") (pinfunction "COM1_10") (pintype "passive"))
      (node (ref "R38") (pin "1") (pinfunction "1_1") (pintype "passive"))
    )
    (net (code "44") (name "/VBUS_FB") (class "Default")
      (node (ref "IC1") (pin "19") (pinfunction "PB1_19") (pintype "bidirectional"))
      (node (ref "R34") (pin "1") (pinfunction "1_1") (pintype "passive"))
      (node (ref "R35") (pin "2") (pinfunction "2_2") (pintype "passive"))
      (node (ref "R36") (pin "2") (pinfunction "2_2") (pintype "passive"))
    )
    (net (code "45") (name "GND") (class "Default")
      (node (ref "C11") (pin "1") (pinfunction "1_1") (pintype "passive"))
      (node (ref "C12") (pin "1") (pinfunction "1_1") (pintype "passive"))
      (node (ref "C14") (pin "2") (pinfunction "2_2") (pintype "passive"))
      (node (ref "C15") (pin "2") (pinfunction "2_2") (pintype "passive"))
      (node (ref "C16") (pin "2") (pinfunction "2_2") (pintype "passive"))
      (node (ref "C17") (pin "2") (pinfunction "2_2") (pintype "passive"))
      (node (ref "C18") (pin "1") (pinfunction "1_1") (pintype "passive"))
      (node (ref "C19") (pin "1") (pinfunction "1_1") (pintype "passive"))
      (node (ref "C2") (pin "1") (pinfunction "1_1") (pintype "passive"))
      (node (ref "C25") (pin "1") (pinfunction "1_1") (pintype "passive"))
      (node (ref "C26") (pin "2") (pinfunction "2_2") (pintype "passive"))
      (node (ref "C27") (pin "2") (pinfunction "2_2") (pintype "passive"))
      (node (ref "C4") (pin "2") (pinfunction "2_2") (pintype "passive"))
      (node (ref "C5") (pin "1") (pinfunction "1_1") (pintype "passive"))
      (node (ref "C6") (pin "1") (pinfunction "1_1") (pintype "passive"))
      (node (ref "C7") (pin "1") (pinfunction "1_1") (pintype "passive"))
      (node (ref "C8") (pin "2") (pinfunction "2_2") (pintype "passive"))
      (node (ref "C9") (pin "2") (pinfunction "2_2") (pintype "passive"))
      (node (ref "D1") (pin "1") (pinfunction "1_1") (pintype "passive"))
      (node (ref "D6") (pin "1") (pinfunction "1_1") (pintype "passive"))
      (node (ref "IC1") (pin "20") (pinfunction "TESTMODE_20") (pintype "passive"))
      (node (ref "IC1") (pin "44") (pinfunction "GND_44") (pintype "power_in"))
      (node (ref "IC1") (pin "49") (pinfunction "EPAD_49") (pintype "power_in"))
      (node (ref "IC5") (pin "1") (pinfunction "S_1") (pintype "passive"))
      (node (ref "IC5") (pin "2") (pinfunction "S_2") (pintype "passive"))
      (node (ref "IC5") (pin "3") (pinfunction "S_3") (pintype "passive"))
      (node (ref "IC7") (pin "3") (pinfunction "GND_3") (pintype "passive"))
      (node (ref "J4") (pin "1") (pinfunction "1_1") (pintype "passive"))
      (node (ref "J5") (pin "3") (pinfunction "3_3") (pintype "passive"))
      (node (ref "Q1") (pin "2") (pinfunction "E_2") (pintype "passive"))
      (node (ref "R11") (pin "1") (pinfunction "1_1") (pintype "passive"))
      (node (ref "R29") (pin "1") (pinfunction "1_1") (pintype "passive"))
      (node (ref "R3") (pin "1") (pinfunction "1_1") (pintype "passive"))
      (node (ref "R35") (pin "1") (pinfunction "1_1") (pintype "passive"))
      (node (ref "R36") (pin "1") (pinfunction "1_1") (pintype "passive"))
      (node (ref "R37") (pin "1") (pinfunction "1_1") (pintype "passive"))
      (node (ref "R42") (pin "1") (pinfunction "1_1") (pintype "passive"))
      (node (ref "R43") (pin "1") (pinfunction "1_1") (pintype "passive"))
      (node (ref "R7") (pin "1") (pinfunction "1_1") (pintype "passive"))
      (node (ref "S1") (pin "1") (pinfunction "1_1") (pintype "passive"))
      (node (ref "S1") (pin "2") (pinfunction "2_2") (pintype "passive"))
      (node (ref "S2") (pin "1") (pinfunction "1_1") (pintype "passive"))
      (node (ref "S2") (pin "2") (pinfunction "2_2") (pintype "passive"))
    )
    (net (code "46") (name "Net-(C5-Pad2)") (class "Default")
      (node (ref "C5") (pin "2") (pinfunction "2_2") (pintype "passive"))
      (node (ref "C6") (pin "2") (pinfunction "2_2") (pintype "passive"))
      (node (ref "C7") (pin "2") (pinfunction "2_2") (pintype "passive"))
      (node (ref "C8") (pin "1") (pinfunction "1_1") (pintype "passive"))
      (node (ref "L1") (pin "1") (pinfunction "1_1") (pintype "passive"))
    )
    (net (code "47") (name "Net-(D5-Pad2)") (class "Default")
      (node (ref "D5") (pin "2") (pinfunction "2_2") (pintype "passive"))
      (node (ref "R29") (pin "2") (pinfunction "2_2") (pintype "passive"))
    )
    (net (code "48") (name "Net-(D6-Pad2)") (class "Default")
      (node (ref "D6") (pin "2") (pinfunction "2_2") (pintype "passive"))
      (node (ref "R32") (pin "2") (pinfunction "2_2") (pintype "passive"))
      (node (ref "R33") (pin "1") (pinfunction "1_1") (pintype "passive"))
    )
    (net (code "49") (name "Net-(IC1-OC_COMP)") (class "Default")
      (node (ref "C11") (pin "2") (pinfunction "2_2") (pintype "passive"))
      (node (ref "IC1") (pin "24") (pinfunction "OC_COMP_24") (pintype "passive"))
      (node (ref "R13") (pin "1") (pinfunction "1_1") (pintype "passive"))
      (node (ref "R14") (pin "1") (pinfunction "1_1") (pintype "passive"))
      (node (ref "R15") (pin "1") (pinfunction "1_1") (pintype "passive"))
      (node (ref "R16") (pin "1") (pinfunction "1_1") (pintype "passive"))
    )
    (net (code "50") (name "Net-(IC1-SW)") (class "Default")
      (node (ref "D1") (pin "2") (pinfunction "2_2") (pintype "passive"))
      (node (ref "IC1") (pin "9") (pinfunction "SW_9") (pintype "power_in"))
      (node (ref "L1") (pin "2") (pinfunction "2_2") (pintype "passive"))
    )
    (net (code "51") (name "Net-(IC1-VBOOTU)") (class "Default")
      (node (ref "C10") (pin "2") (pinfunction "2_2") (pintype "passive"))
      (node (ref "IC1") (pin "35") (pinfunction "VBOOTU_35") (pintype "passive"))
    )
    (net (code "52") (name "Net-(IC1-VBOOTV)") (class "Default")
      (node (ref "C3") (pin "2") (pinfunction "2_2") (pintype "passive"))
      (node (ref "IC1") (pin "31") (pinfunction "VBOOTV_31") (pintype "passive"))
    )
    (net (code "53") (name "Net-(IC1-VBOOTW)") (class "Default")
      (node (ref "C1") (pin "2") (pinfunction "2_2") (pintype "passive"))
      (node (ref "IC1") (pin "27") (pinfunction "VBOOTW_27") (pintype "passive"))
    )
    (net (code "54") (name "Net-(IC5-D)") (class "Default")
      (node (ref "D4") (pin "1") (pinfunction "1_1") (pintype "passive"))
      (node (ref "IC5") (pin "5") (pinfunction "D_5") (pintype "passive"))
      (node (ref "J1") (pin "3") (pinfunction "3_3") (pintype "passive"))
      (node (ref "J1") (pin "4") (pinfunction "4_4") (pintype "passive"))
    )
    (net (code "55") (name "Net-(IC5-G)") (class "Default")
      (node (ref "IC5") (pin "4") (pinfunction "G_4") (pintype "passive"))
      (node (ref "R32") (pin "1") (pinfunction "1_1") (pintype "passive"))
    )
    (net (code "56") (name "Net-(IC6-D)") (class "Default")
      (node (ref "IC6") (pin "5") (pinfunction "D_5") (pintype "passive"))
      (node (ref "J3") (pin "2") (pinfunction "2_2") (pintype "passive"))
    )
    (net (code "57") (name "Net-(IC6-G)") (class "Default")
      (node (ref "IC6") (pin "4") (pinfunction "G_4") (pintype "passive"))
      (node (ref "Q1") (pin "3") (pinfunction "C_3") (pintype "passive"))
      (node (ref "R41") (pin "2") (pinfunction "2_2") (pintype "passive"))
    )
    (net (code "58") (name "Net-(Q1-B)") (class "Default")
      (node (ref "IC6") (pin "1") (pinfunction "S_1") (pintype "passive"))
      (node (ref "IC6") (pin "2") (pinfunction "S_2") (pintype "passive"))
      (node (ref "IC6") (pin "3") (pinfunction "S_3") (pintype "passive"))
      (node (ref "Q1") (pin "1") (pinfunction "B_1") (pintype "passive"))
      (node (ref "R43") (pin "2") (pinfunction "2_2") (pintype "passive"))
    )
    (net (code "59") (name "Net-(R17-Pad1)") (class "Default")
      (node (ref "R17") (pin "1") (pinfunction "1_1") (pintype "passive"))
      (node (ref "R18") (pin "1") (pinfunction "1_1") (pintype "passive"))
      (node (ref "S1") (pin "3") (pinfunction "3_3") (pintype "passive"))
      (node (ref "S1") (pin "4") (pinfunction "4_4") (pintype "passive"))
    )
    (net (code "60") (name "unconnected-(IC1-3FG_PA7-Pad18)") (class "Default")
      (node (ref "IC1") (pin "18") (pinfunction "3FG_PA7_18") (pintype "bidirectional"))
    )
    (net (code "61") (name "unconnected-(IC1-OP1N-Pad22)") (class "Default")
      (node (ref "IC1") (pin "22") (pinfunction "OP1N_22") (pintype "input"))
    )
    (net (code "62") (name "unconnected-(IC1-OP1O-Pad21)") (class "Default")
      (node (ref "IC1") (pin "21") (pinfunction "OP1O_21") (pintype "output"))
    )
    (net (code "63") (name "unconnected-(IC1-OP1P-Pad23)") (class "Default")
      (node (ref "IC1") (pin "23") (pinfunction "OP1P_23") (pintype "input"))
    )
    (net (code "64") (name "unconnected-(J4-Pad2)") (class "Default")
      (node (ref "J4") (pin "2") (pinfunction "2_2") (pintype "passive+no_connect"))
    )
    (net (code "65") (name "unconnected-(J4-Pad6)") (class "Default")
      (node (ref "J4") (pin "6") (pinfunction "6_6") (pintype "passive+no_connect"))
    )
    (net (code "66") (name "unconnected-(J5-Pad6)") (class "Default")
      (node (ref "J5") (pin "6") (pinfunction "6_6") (pintype "passive+no_connect"))
    )
  )
)
